# PAGE3_POWER.net
KiCad netlist of a schematic drawn in Altium Designer
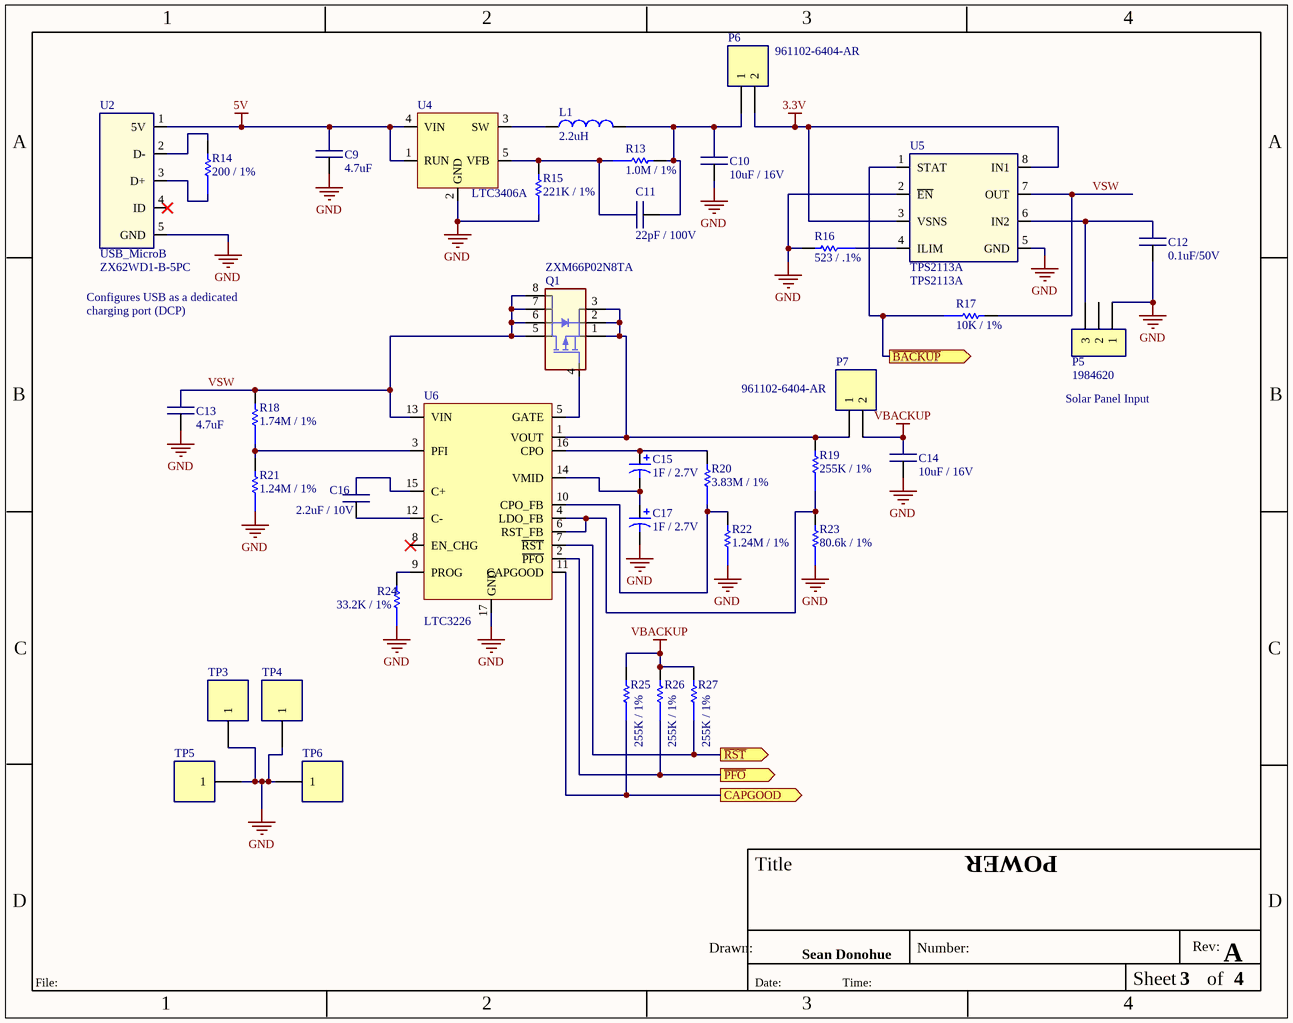
[diagram p0: PAGE3_POWER.SchDoc]

(export (version "E")
  (design (tool "Eeschema 10.0.6"))
  (components
    (comp (ref "C9")
      (value "4.7uF")
      (footprint "0805")
      (description "CAP 4.7uF 16V X7R 0805")
      (fields (field (name "MFG") "Murata") (field (name "Comment") "cap"))
      (libsource (lib "eetrex comp db") (part "cap"))
    )
    (comp (ref "C10")
      (value "10uF / 16V")
      (footprint "0603")
      (description "CAP CER 10UF 16V X5R 0603")
      (fields (field (name "MFG") "Taiyo Uden") (field (name "Comment") "cap"))
      (libsource (lib "eetrex comp db") (part "cap"))
    )
    (comp (ref "C11")
      (value "22pF / 100V")
      (footprint "0603")
      (description "CAP CER 22PF 100V NP0 0603")
      (fields (field (name "MFG") "KEMET") (field (name "Comment") "cap"))
      (libsource (lib "eetrex comp db") (part "cap"))
    )
    (comp (ref "C12")
      (value "0.1uF/50V")
      (footprint "0603")
      (description "CAP CER 0.1UF 50V 10% X7R 0603")
      (fields (field (name "MFG") "Murata") (field (name "Comment") "cap"))
      (libsource (lib "eetrex comp db") (part "cap"))
    )
    (comp (ref "C13")
      (value "4.7uF")
      (footprint "0805")
      (description "CAP 4.7uF 16V X7R 0805")
      (fields (field (name "MFG") "Murata") (field (name "Comment") "cap"))
      (libsource (lib "eetrex comp db") (part "cap"))
    )
    (comp (ref "C14")
      (value "10uF / 16V")
      (footprint "0603")
      (description "CAP CER 10UF 16V X5R 0603")
      (fields (field (name "MFG") "Taiyo Uden") (field (name "Comment") "cap"))
      (libsource (lib "eetrex comp db") (part "cap"))
    )
    (comp (ref "C15")
      (value "1F / 2.7V")
      (footprint "Cap8x11_5")
      (description "CAP 1F 2.7V THROUGH HOLE")
      (fields (field (name "MFG") "Maxwell") (field (name "Comment") "Cap Pol"))
      (libsource (lib "eetrex comp db") (part "Cap Pol"))
    )
    (comp (ref "C16")
      (value "2.2uF / 10V")
      (footprint "0603")
      (description "CAP CER 2.2UF 10V X7R 0603")
      (fields (field (name "MFG") "Samsung") (field (name "Comment") "cap"))
      (libsource (lib "eetrex comp db") (part "cap"))
    )
    (comp (ref "C17")
      (value "1F / 2.7V")
      (footprint "Cap8x11_5")
      (description "CAP 1F 2.7V THROUGH HOLE")
      (fields (field (name "MFG") "Maxwell") (field (name "Comment") "Cap Pol"))
      (libsource (lib "eetrex comp db") (part "Cap Pol"))
    )
    (comp (ref "L1")
      (value "2.2uH")
      (footprint "LQH32C")
      (description "FIXED IND 2.2UH 790MA 97 MOHM")
      (fields (field (name "MFG") "Murata") (field (name "Comment") "Inductor"))
      (libsource (lib "eetrex comp db") (part "Inductor"))
    )
    (comp (ref "P5")
      (value "1984620")
      (footprint "CONN_PHOENIX_3P_1984620")
      (description "CONN TERM BLOCK T/H 3POS 3.5MM")
      (fields (field (name "MFG") "Phoenix Contact") (field (name "Comment") "Header 3"))
      (libsource (lib "eetrex comp db") (part "Header 3"))
    )
    (comp (ref "P6")
      (value "961102-6404-AR")
      (footprint "HDR1X2")
      (description "CONN HEADER VERT SGL 2POS GOLD")
      (fields (field (name "MFG") "3M") (field (name "Comment") "Header 2"))
      (libsource (lib "eetrex comp db") (part "Header 2"))
    )
    (comp (ref "P7")
      (value "961102-6404-AR")
      (footprint "HDR1X2")
      (description "CONN HEADER VERT SGL 2POS GOLD")
      (fields (field (name "MFG") "3M") (field (name "Comment") "Header 2"))
      (libsource (lib "eetrex comp db") (part "Header 2"))
    )
    (comp (ref "Q1")
      (value "ZXM66P02N8TA")
      (footprint "SO-8")
      (description "MOSFET P-CH 20V 8A 8-SOIC")
      (fields (field (name "MFG") "Diodes inc") (field (name "Comment") "PMOS_POWER-8"))
      (libsource (lib "eetrex comp db") (part "PMOS_POWER-8"))
    )
    (comp (ref "R13")
      (value "1.0M / 1%")
      (footprint "0603")
      (description "RES 1M OHM 1% 1/10W 0603 SMD")
      (fields (field (name "MFG") "Panasonic") (field (name "Comment") "Res"))
      (libsource (lib "eetrex comp db") (part "Res"))
    )
    (comp (ref "R14")
      (value "200 / 1%")
      (footprint "0603")
      (description "RES 200 OHM 1% 1/10W 0603 SMD")
      (fields (field (name "MFG") "Panasonic") (field (name "Comment") "Res"))
      (libsource (lib "eetrex comp db") (part "Res"))
    )
    (comp (ref "R15")
      (value "221K / 1%")
      (footprint "0603")
      (description "RES 221K OHM 1% 1/10W 0603 SMD")
      (fields (field (name "MFG") "Panasonic") (field (name "Comment") "Res"))
      (libsource (lib "eetrex comp db") (part "Res"))
    )
    (comp (ref "R16")
      (value "523 / .1%")
      (footprint "0603")
      (description "RES 523 OHM 1/10W .1% 0603 SMD")
      (fields (field (name "MFG") "Susumu") (field (name "Comment") "Res"))
      (libsource (lib "eetrex comp db") (part "Res"))
    )
    (comp (ref "R17")
      (value "10K / 1%")
      (footprint "0603")
      (description "RES 10K OHM 1% 1/8W 0603 SMD")
      (fields (field (name "MFG") "Vishay") (field (name "Comment") "Res"))
      (libsource (lib "eetrex comp db") (part "Res"))
    )
    (comp (ref "R18")
      (value "1.74M / 1%")
      (footprint "0603")
      (description "RES 1.74M OHM 1% 1/10W 0603 SMD")
      (fields (field (name "MFG") "Vishay") (field (name "Comment") "Res"))
      (libsource (lib "eetrex comp db") (part "Res"))
    )
    (comp (ref "R19")
      (value "255K / 1%")
      (footprint "0603")
      (description "RES 255K OHM 1% 1/10W 0603 SMD")
      (fields (field (name "MFG") "Panasonic") (field (name "Comment") "Res"))
      (libsource (lib "eetrex comp db") (part "Res"))
    )
    (comp (ref "R20")
      (value "3.83M / 1%")
      (footprint "0603")
      (description "RES 3.83M OHM 1% 1/10W 0603 SMD")
      (fields (field (name "MFG") "Vishay") (field (name "Comment") "Res"))
      (libsource (lib "eetrex comp db") (part "Res"))
    )
    (comp (ref "R21")
      (value "1.24M / 1%")
      (footprint "0603")
      (description "RES 1.24M OHM 1% 1/10W 0603 SMD")
      (fields (field (name "MFG") "Vishay") (field (name "Comment") "Res"))
      (libsource (lib "eetrex comp db") (part "Res"))
    )
    (comp (ref "R22")
      (value "1.24M / 1%")
      (footprint "0603")
      (description "RES 1.24M OHM 1% 1/10W 0603 SMD")
      (fields (field (name "MFG") "Vishay") (field (name "Comment") "Res"))
      (libsource (lib "eetrex comp db") (part "Res"))
    )
    (comp (ref "R23")
      (value "80.6k / 1%")
      (footprint "0603")
      (description "RES 80.6K OHM 1% 1/10W 0603 SMD")
      (fields (field (name "MFG") "Panasonic") (field (name "Comment") "Res"))
      (libsource (lib "eetrex comp db") (part "Res"))
    )
    (comp (ref "R24")
      (value "33.2K / 1%")
      (footprint "0603")
      (description "RES 33.2K OHM 1% 1/10W 0603 SMD")
      (fields (field (name "MFG") "Panasonic") (field (name "Comment") "Res"))
      (libsource (lib "eetrex comp db") (part "Res"))
    )
    (comp (ref "R25")
      (value "255K / 1%")
      (footprint "0603")
      (description "RES 255K OHM 1% 1/10W 0603 SMD")
      (fields (field (name "MFG") "Panasonic") (field (name "Comment") "Res"))
      (libsource (lib "eetrex comp db") (part "Res"))
    )
    (comp (ref "R26")
      (value "255K / 1%")
      (footprint "0603")
      (description "RES 255K OHM 1% 1/10W 0603 SMD")
      (fields (field (name "MFG") "Panasonic") (field (name "Comment") "Res"))
      (libsource (lib "eetrex comp db") (part "Res"))
    )
    (comp (ref "R27")
      (value "255K / 1%")
      (footprint "0603")
      (description "RES 255K OHM 1% 1/10W 0603 SMD")
      (fields (field (name "MFG") "Panasonic") (field (name "Comment") "Res"))
      (libsource (lib "eetrex comp db") (part "Res"))
    )
    (comp (ref "TP3")
      (value "Header 1")
      (footprint "HDR1")
      (description "CONN HEADER 1POS .330 tall, TIN")
      (fields (field (name "MFG") "Samtec"))
      (libsource (lib "eetrex comp db") (part "Header 1"))
    )
    (comp (ref "TP4")
      (value "Header 1")
      (footprint "HDR1")
      (description "CONN HEADER 1POS .330 tall, TIN")
      (fields (field (name "MFG") "Samtec"))
      (libsource (lib "eetrex comp db") (part "Header 1"))
    )
    (comp (ref "TP5")
      (value "Header 1")
      (footprint "HDR1")
      (description "CONN HEADER 1POS .330 tall, TIN")
      (fields (field (name "MFG") "Samtec"))
      (libsource (lib "") (part "Header 1_1"))
    )
    (comp (ref "TP6")
      (value "Header 1")
      (footprint "HDR1")
      (description "CONN HEADER 1POS .330 tall, TIN")
      (fields (field (name "MFG") "Samtec"))
      (libsource (lib "") (part "Header 1_2"))
    )
    (comp (ref "U2")
      (value "USB_MicroB")
      (footprint "ZX62WD1-B-5PC")
      (description "CONN RCPT MICRO USB B SPLASH PRF")
      (fields (field (name "ALTIUM_VALUE") "ZX62WD1-B-5PC") (field (name "MFG") "Hirose"))
      (libsource (lib "eetrex comp db") (part "USB_MicroB"))
    )
    (comp (ref "U4")
      (value "LTC3406A")
      (footprint "TSOT-23-5")
      (description "IC REG BUCK ADJ 0.6A SYNC TSOT23")
      (fields (field (name "MFG") "Linear Tech"))
      (libsource (lib "eetrex comp db") (part "LTC3406A"))
    )
    (comp (ref "U5")
      (value "TPS2113A")
      (footprint "TSSOP-8")
      (description "IC OR CTRLR SRC SELECT 8TSSOP")
      (fields (field (name "ALTIUM_VALUE") "TPS2113A") (field (name "MFG") "Texas Instruments"))
      (libsource (lib "eetrex comp db") (part "TPS2113A"))
    )
    (comp (ref "U6")
      (value "LTC3226")
      (footprint "WFQFN-16")
      (description "IC 2CELL SUPERCAP CHARGE 16QFN")
      (fields (field (name "MFG") "Linear Tech"))
      (libsource (lib "eetrex comp db") (part "LTC3226"))
    )
  )
  (nets
    (net (code "1") (name "/CAPGOOD") (class "Default")
      (node (ref "R25") (pin "1") (pinfunction "1_1") (pintype "passive"))
      (node (ref "U6") (pin "11") (pinfunction "CAPGOOD_11") (pintype "passive"))
    )
    (net (code "2") (name "/VSW") (class "Default")
      (node (ref "C13") (pin "1") (pinfunction "1_1") (pintype "passive"))
      (node (ref "Q1") (pin "5") (pinfunction "D_5") (pintype "passive"))
      (node (ref "Q1") (pin "6") (pinfunction "D_6") (pintype "passive"))
      (node (ref "Q1") (pin "7") (pinfunction "D_7") (pintype "passive"))
      (node (ref "Q1") (pin "8") (pinfunction "D_8") (pintype "passive"))
      (node (ref "R17") (pin "2") (pinfunction "2_2") (pintype "passive"))
      (node (ref "R18") (pin "2") (pinfunction "2_2") (pintype "passive"))
      (node (ref "U5") (pin "7") (pinfunction "OUT_7") (pintype "passive"))
      (node (ref "U6") (pin "13") (pinfunction "VIN_13") (pintype "passive"))
    )
    (net (code "3") (name "/~{BACKUP}") (class "Default")
      (node (ref "R17") (pin "1") (pinfunction "1_1") (pintype "passive"))
      (node (ref "U5") (pin "1") (pinfunction "STAT_1") (pintype "passive"))
    )
    (net (code "4") (name "/~{PFO}") (class "Default")
      (node (ref "R26") (pin "1") (pinfunction "1_1") (pintype "passive"))
      (node (ref "U6") (pin "2") (pinfunction "~{PFO}_2") (pintype "passive"))
    )
    (net (code "5") (name "/~{RST}") (class "Default")
      (node (ref "R27") (pin "1") (pinfunction "1_1") (pintype "passive"))
      (node (ref "U6") (pin "7") (pinfunction "~{RST}_7") (pintype "passive"))
    )
    (net (code "6") (name "3.3V") (class "Default")
      (node (ref "P6") (pin "2") (pinfunction "2_2") (pintype "passive"))
      (node (ref "U5") (pin "3") (pinfunction "VSNS_3") (pintype "passive"))
      (node (ref "U5") (pin "8") (pinfunction "IN1_8") (pintype "passive"))
    )
    (net (code "7") (name "5V") (class "Default")
      (node (ref "C9") (pin "1") (pinfunction "1_1") (pintype "passive"))
      (node (ref "U2") (pin "1") (pinfunction "5V_1") (pintype "passive"))
      (node (ref "U4") (pin "1") (pinfunction "RUN_1") (pintype "passive"))
      (node (ref "U4") (pin "4") (pinfunction "VIN_4") (pintype "passive"))
    )
    (net (code "8") (name "GND") (class "Default")
      (node (ref "C10") (pin "2") (pinfunction "2_2") (pintype "passive"))
      (node (ref "C12") (pin "2") (pinfunction "2_2") (pintype "passive"))
      (node (ref "C13") (pin "2") (pinfunction "2_2") (pintype "passive"))
      (node (ref "C14") (pin "2") (pinfunction "2_2") (pintype "passive"))
      (node (ref "C17") (pin "2") (pinfunction "2_2") (pintype "passive"))
      (node (ref "C9") (pin "2") (pinfunction "2_2") (pintype "passive"))
      (node (ref "P5") (pin "1") (pinfunction "1_1") (pintype "passive"))
      (node (ref "R15") (pin "1") (pinfunction "1_1") (pintype "passive"))
      (node (ref "R16") (pin "2") (pinfunction "2_2") (pintype "passive"))
      (node (ref "R21") (pin "1") (pinfunction "1_1") (pintype "passive"))
      (node (ref "R22") (pin "1") (pinfunction "1_1") (pintype "passive"))
      (node (ref "R23") (pin "1") (pinfunction "1_1") (pintype "passive"))
      (node (ref "R24") (pin "1") (pinfunction "1_1") (pintype "passive"))
      (node (ref "TP3") (pin "1") (pinfunction "1_1") (pintype "passive"))
      (node (ref "TP4") (pin "1") (pinfunction "1_1") (pintype "passive"))
      (node (ref "TP5") (pin "1") (pinfunction "1_1") (pintype "passive"))
      (node (ref "TP6") (pin "1") (pinfunction "1_1") (pintype "passive"))
      (node (ref "U2") (pin "5") (pinfunction "GND_5") (pintype "passive"))
      (node (ref "U4") (pin "2") (pinfunction "GND_2") (pintype "passive"))
      (node (ref "U5") (pin "2") (pinfunction "~{EN}_2") (pintype "passive"))
      (node (ref "U5") (pin "5") (pinfunction "GND_5") (pintype "passive"))
      (node (ref "U6") (pin "17") (pinfunction "GND_17") (pintype "passive"))
    )
    (net (code "9") (name "Net-(C10-Pad1)") (class "Default")
      (node (ref "C10") (pin "1") (pinfunction "1_1") (pintype "passive"))
      (node (ref "C11") (pin "2") (pinfunction "2_2") (pintype "passive"))
      (node (ref "L1") (pin "2") (pinfunction "2_2") (pintype "passive"))
      (node (ref "P6") (pin "1") (pinfunction "1_1") (pintype "passive"))
      (node (ref "R13") (pin "2") (pinfunction "2_2") (pintype "passive"))
    )
    (net (code "10") (name "Net-(Q1-G)") (class "Default")
      (node (ref "Q1") (pin "4") (pinfunction "G_4") (pintype "passive"))
      (node (ref "U6") (pin "5") (pinfunction "GATE_5") (pintype "passive"))
    )
    (net (code "11") (name "Net-(U2-D+)") (class "Default")
      (node (ref "R14") (pin "1") (pinfunction "1_1") (pintype "passive"))
      (node (ref "U2") (pin "3") (pinfunction "D+_3") (pintype "passive"))
    )
    (net (code "12") (name "Net-(U2-D-)") (class "Default")
      (node (ref "R14") (pin "2") (pinfunction "2_2") (pintype "passive"))
      (node (ref "U2") (pin "2") (pinfunction "D-_2") (pintype "passive"))
    )
    (net (code "13") (name "Net-(U4-SW)") (class "Default")
      (node (ref "L1") (pin "1") (pinfunction "1_1") (pintype "passive"))
      (node (ref "U4") (pin "3") (pinfunction "SW_3") (pintype "passive"))
    )
    (net (code "14") (name "Net-(U4-VFB)") (class "Default")
      (node (ref "C11") (pin "1") (pinfunction "1_1") (pintype "passive"))
      (node (ref "R13") (pin "1") (pinfunction "1_1") (pintype "passive"))
      (node (ref "R15") (pin "2") (pinfunction "2_2") (pintype "passive"))
      (node (ref "U4") (pin "5") (pinfunction "VFB_5") (pintype "passive"))
    )
    (net (code "15") (name "Net-(U5-ILIM)") (class "Default")
      (node (ref "R16") (pin "1") (pinfunction "1_1") (pintype "passive"))
      (node (ref "U5") (pin "4") (pinfunction "ILIM_4") (pintype "passive"))
    )
    (net (code "16") (name "Net-(U5-IN2)") (class "Default")
      (node (ref "C12") (pin "1") (pinfunction "1_1") (pintype "passive"))
      (node (ref "P5") (pin "3") (pinfunction "3_3") (pintype "passive"))
      (node (ref "U5") (pin "6") (pinfunction "IN2_6") (pintype "passive"))
    )
    (net (code "17") (name "Net-(U6-C+)") (class "Default")
      (node (ref "C16") (pin "1") (pinfunction "1_1") (pintype "passive"))
      (node (ref "U6") (pin "15") (pinfunction "C+_15") (pintype "passive"))
    )
    (net (code "18") (name "Net-(U6-C-)") (class "Default")
      (node (ref "C16") (pin "2") (pinfunction "2_2") (pintype "passive"))
      (node (ref "U6") (pin "12") (pinfunction "C-_12") (pintype "passive"))
    )
    (net (code "19") (name "Net-(U6-CPO)") (class "Default")
      (node (ref "C15") (pin "1") (pinfunction "1_1") (pintype "passive"))
      (node (ref "R20") (pin "2") (pinfunction "2_2") (pintype "passive"))
      (node (ref "U6") (pin "16") (pinfunction "CPO_16") (pintype "passive"))
    )
    (net (code "20") (name "Net-(U6-CPO_FB)") (class "Default")
      (node (ref "R20") (pin "1") (pinfunction "1_1") (pintype "passive"))
      (node (ref "R22") (pin "2") (pinfunction "2_2") (pintype "passive"))
      (node (ref "U6") (pin "10") (pinfunction "CPO_FB_10") (pintype "passive"))
    )
    (net (code "21") (name "Net-(U6-LDO_FB)") (class "Default")
      (node (ref "R19") (pin "1") (pinfunction "1_1") (pintype "passive"))
      (node (ref "R23") (pin "2") (pinfunction "2_2") (pintype "passive"))
      (node (ref "U6") (pin "4") (pinfunction "LDO_FB_4") (pintype "passive"))
      (node (ref "U6") (pin "6") (pinfunction "RST_FB_6") (pintype "passive"))
    )
    (net (code "22") (name "Net-(U6-PFI)") (class "Default")
      (node (ref "R18") (pin "1") (pinfunction "1_1") (pintype "passive"))
      (node (ref "R21") (pin "2") (pinfunction "2_2") (pintype "passive"))
      (node (ref "U6") (pin "3") (pinfunction "PFI_3") (pintype "passive"))
    )
    (net (code "23") (name "Net-(U6-PROG)") (class "Default")
      (node (ref "R24") (pin "2") (pinfunction "2_2") (pintype "passive"))
      (node (ref "U6") (pin "9") (pinfunction "PROG_9") (pintype "passive"))
    )
    (net (code "24") (name "Net-(U6-VMID)") (class "Default")
      (node (ref "C15") (pin "2") (pinfunction "2_2") (pintype "passive"))
      (node (ref "C17") (pin "1") (pinfunction "1_1") (pintype "passive"))
      (node (ref "U6") (pin "14") (pinfunction "VMID_14") (pintype "passive"))
    )
    (net (code "25") (name "Net-(U6-VOUT)") (class "Default")
      (node (ref "P7") (pin "1") (pinfunction "1_1") (pintype "passive"))
      (node (ref "Q1") (pin "1") (pinfunction "S_1") (pintype "passive"))
      (node (ref "Q1") (pin "2") (pinfunction "S_2") (pintype "passive"))
      (node (ref "Q1") (pin "3") (pinfunction "S_3") (pintype "passive"))
      (node (ref "R19") (pin "2") (pinfunction "2_2") (pintype "passive"))
      (node (ref "U6") (pin "1") (pinfunction "VOUT_1") (pintype "passive"))
    )
    (net (code "26") (name "VBACKUP") (class "Default")
      (node (ref "C14") (pin "1") (pinfunction "1_1") (pintype "passive"))
      (node (ref "P7") (pin "2") (pinfunction "2_2") (pintype "passive"))
      (node (ref "R25") (pin "2") (pinfunction "2_2") (pintype "passive"))
      (node (ref "R26") (pin "2") (pinfunction "2_2") (pintype "passive"))
      (node (ref "R27") (pin "2") (pinfunction "2_2") (pintype "passive"))
    )
    (net (code "27") (name "unconnected-(P5-Pad2)") (class "Default")
      (node (ref "P5") (pin "2") (pinfunction "2_2") (pintype "passive"))
    )
    (net (code "28") (name "unconnected-(U2-ID-Pad4)") (class "Default")
      (node (ref "U2") (pin "4") (pinfunction "ID_4") (pintype "passive+no_connect"))
    )
    (net (code "29") (name "unconnected-(U6-EN_CHG-Pad8)") (class "Default")
      (node (ref "U6") (pin "8") (pinfunction "EN_CHG_8") (pintype "passive+no_connect"))
    )
  )
)
